# IMX7S_MEMORY.net
KiCad netlist of a schematic drawn in Altium Designer
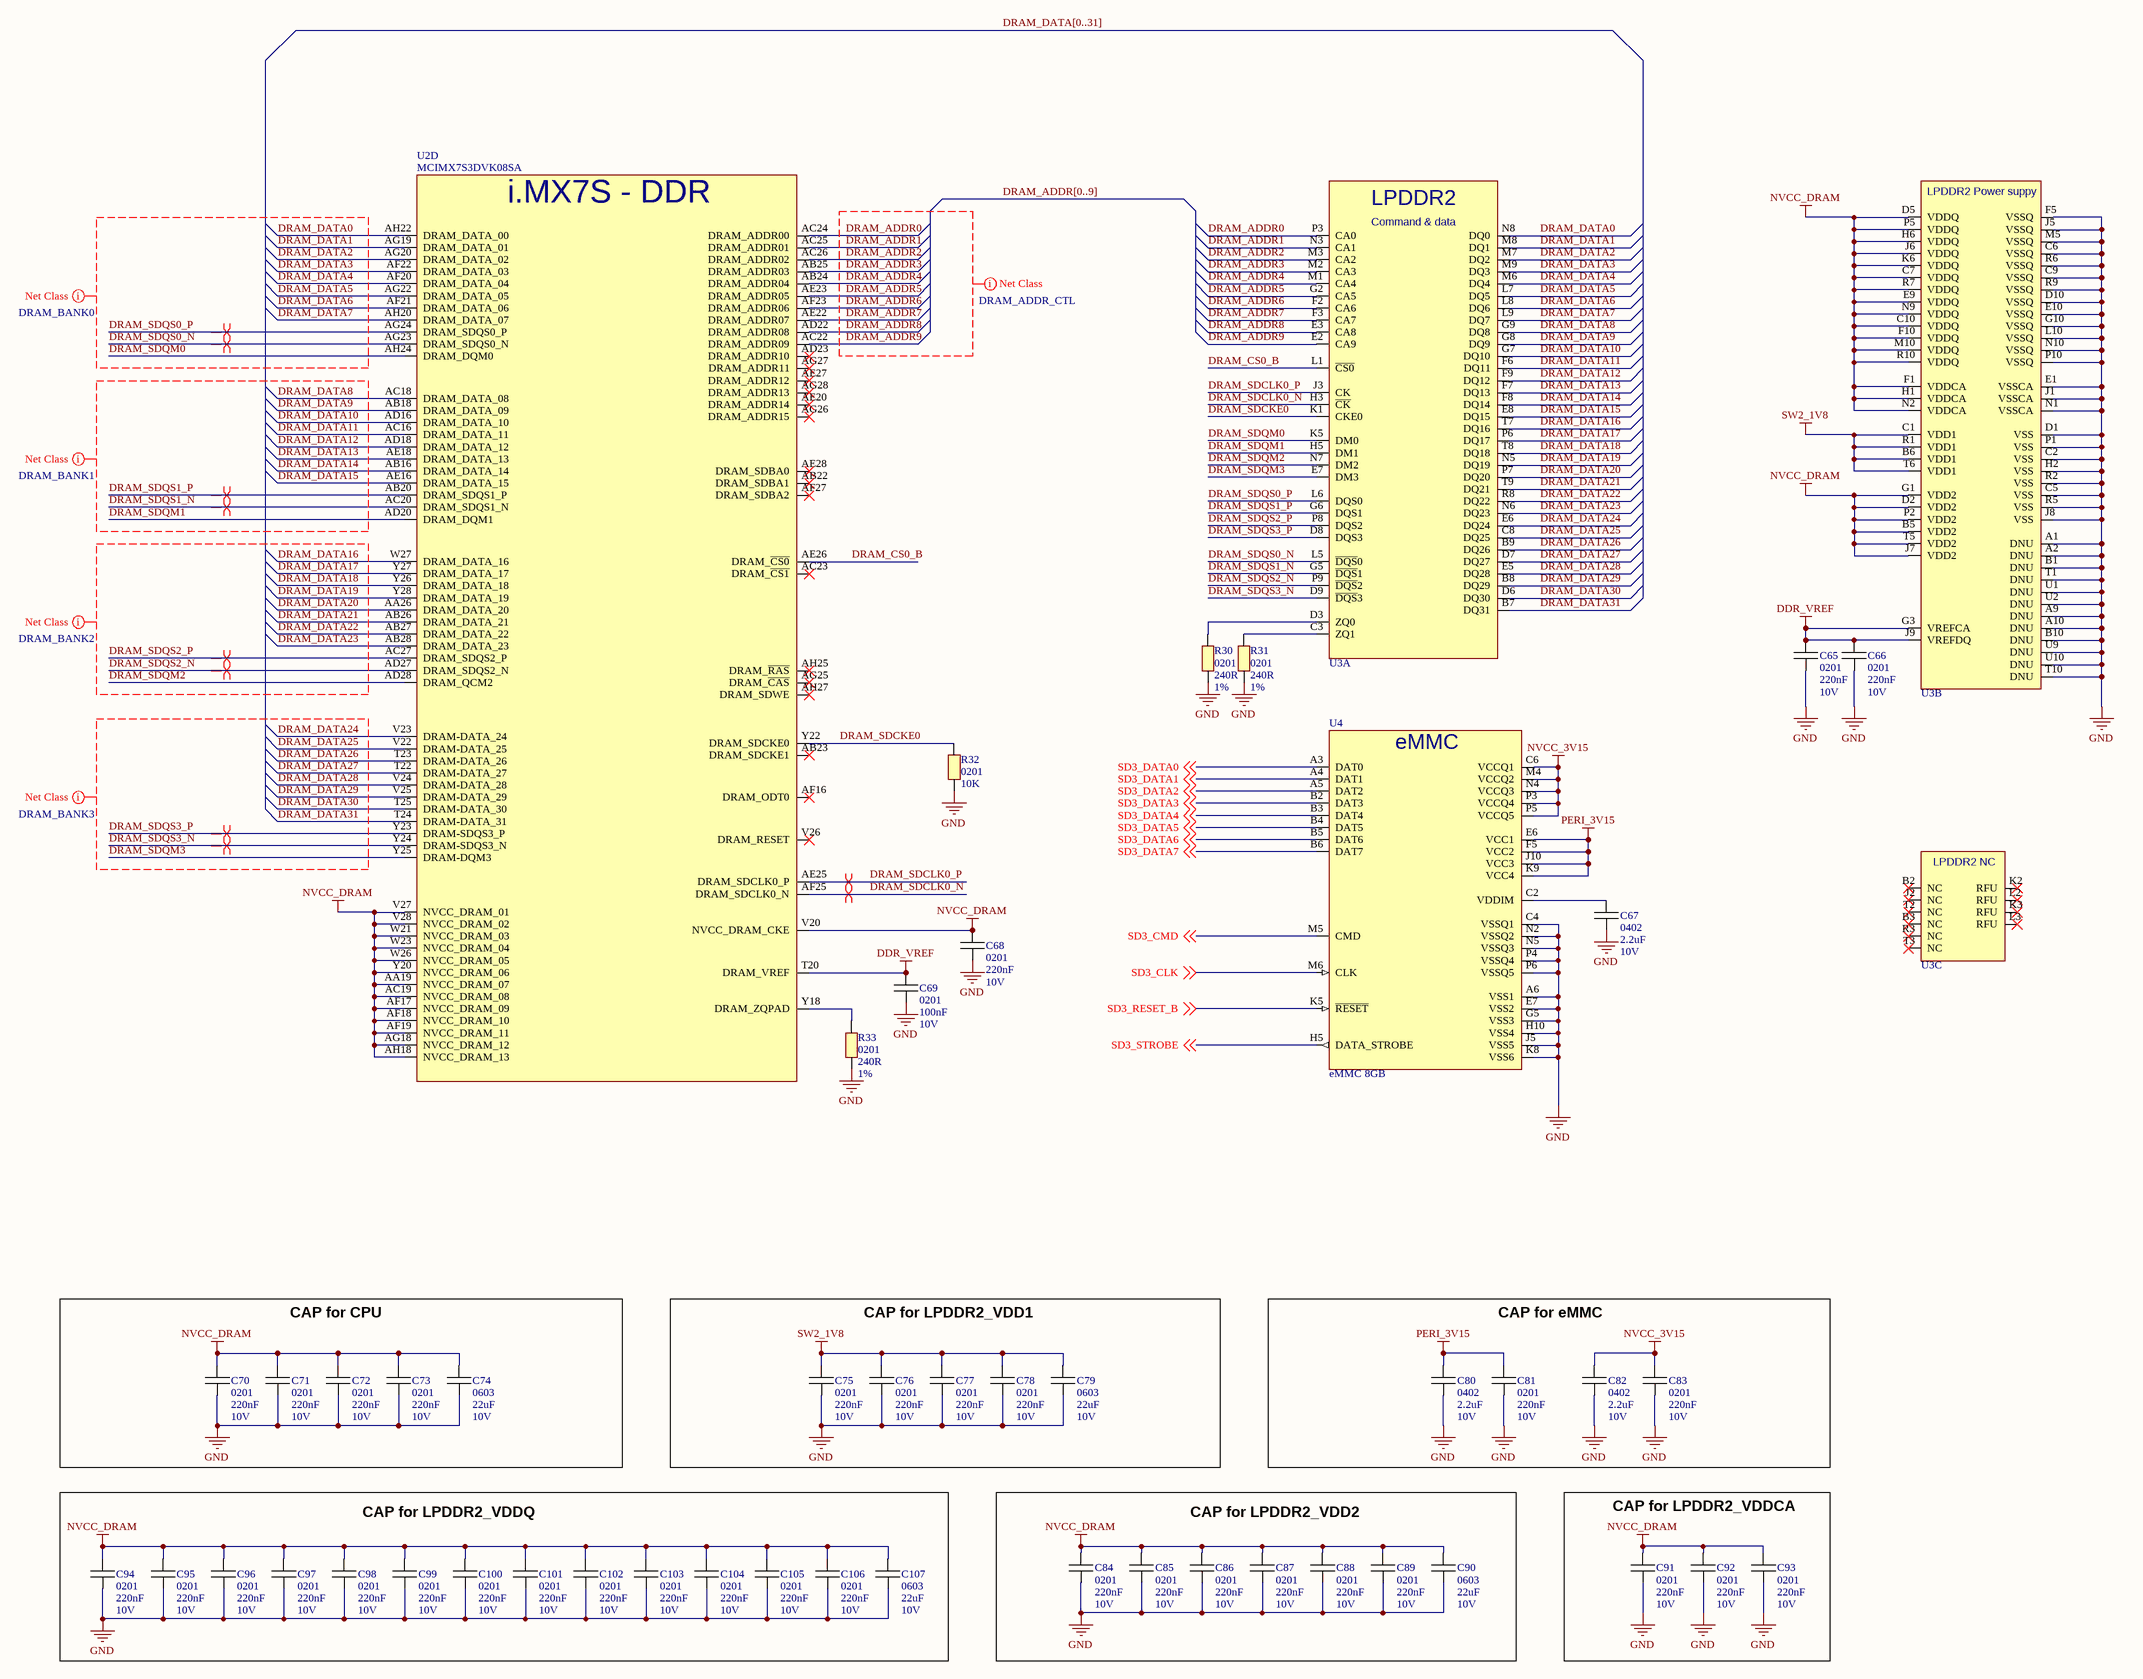
[diagram p0: IMX7S_MEMORY.SchDoc]

(export (version "E")
  (design (tool "Eeschema 10.0.6"))
  (components
    (comp (ref "C65")
      (value "220nF")
      (footprint "C0201")
      (fields
        (field (name "PACKAGE") "0201")
        (field (name "VOLTAGE") "10V")
        (field (name "TOLERANCE") "10%")
        (field (name "Comment") "C0201")
      )
      (libsource (lib "Schlib_IMX7") (part "C0201"))
    )
    (comp (ref "C66")
      (value "220nF")
      (footprint "C0201")
      (fields
        (field (name "PACKAGE") "0201")
        (field (name "VOLTAGE") "10V")
        (field (name "TOLERANCE") "10%")
        (field (name "Comment") "C0201")
      )
      (libsource (lib "Schlib_IMX7") (part "C0201"))
    )
    (comp (ref "C67")
      (value "2.2uF")
      (footprint "C0402")
      (fields
        (field (name "PACKAGE") "0402")
        (field (name "VOLTAGE") "10V")
        (field (name "TOLERANCE") "20%")
        (field (name "Comment") "C0402")
      )
      (libsource (lib "Schlib_IMX7") (part "C0402"))
    )
    (comp (ref "C68")
      (value "220nF")
      (footprint "C0201")
      (fields
        (field (name "PACKAGE") "0201")
        (field (name "VOLTAGE") "10V")
        (field (name "TOLERANCE") "10%")
        (field (name "Comment") "C0201")
      )
      (libsource (lib "Schlib_IMX7") (part "C0201"))
    )
    (comp (ref "C69")
      (value "100nF")
      (footprint "C0201")
      (fields
        (field (name "PACKAGE") "0201")
        (field (name "VOLTAGE") "10V")
        (field (name "TOLERANCE") "10%")
        (field (name "Comment") "C0201")
      )
      (libsource (lib "Schlib_IMX7") (part "C0201"))
    )
    (comp (ref "C70")
      (value "220nF")
      (footprint "C0201")
      (fields
        (field (name "PACKAGE") "0201")
        (field (name "VOLTAGE") "10V")
        (field (name "TOLERANCE") "10%")
        (field (name "Comment") "C0201")
      )
      (libsource (lib "Schlib_IMX7") (part "C0201"))
    )
    (comp (ref "C71")
      (value "220nF")
      (footprint "C0201")
      (fields
        (field (name "PACKAGE") "0201")
        (field (name "VOLTAGE") "10V")
        (field (name "TOLERANCE") "10%")
        (field (name "Comment") "C0201")
      )
      (libsource (lib "Schlib_IMX7") (part "C0201"))
    )
    (comp (ref "C72")
      (value "220nF")
      (footprint "C0201")
      (fields
        (field (name "PACKAGE") "0201")
        (field (name "VOLTAGE") "10V")
        (field (name "TOLERANCE") "10%")
        (field (name "Comment") "C0201")
      )
      (libsource (lib "Schlib_IMX7") (part "C0201"))
    )
    (comp (ref "C73")
      (value "220nF")
      (footprint "C0201")
      (fields
        (field (name "PACKAGE") "0201")
        (field (name "VOLTAGE") "10V")
        (field (name "TOLERANCE") "10%")
        (field (name "Comment") "C0201")
      )
      (libsource (lib "Schlib_IMX7") (part "C0201"))
    )
    (comp (ref "C74")
      (value "22uF")
      (footprint "C0603")
      (description "CAP, MLCC, X5R, 22UF, 10V, 0603")
      (fields
        (field (name "PACKAGE") "0603")
        (field (name "VOLTAGE") "10V")
        (field (name "TOLERANCE") "20%")
        (field (name "Comment") "C0603")
      )
      (libsource (lib "Schlib_IMX7") (part "C0603"))
    )
    (comp (ref "C75")
      (value "220nF")
      (footprint "C0201")
      (fields
        (field (name "PACKAGE") "0201")
        (field (name "VOLTAGE") "10V")
        (field (name "TOLERANCE") "10%")
        (field (name "Comment") "C0201")
      )
      (libsource (lib "Schlib_IMX7") (part "C0201"))
    )
    (comp (ref "C76")
      (value "220nF")
      (footprint "C0201")
      (fields
        (field (name "PACKAGE") "0201")
        (field (name "VOLTAGE") "10V")
        (field (name "TOLERANCE") "10%")
        (field (name "Comment") "C0201")
      )
      (libsource (lib "Schlib_IMX7") (part "C0201"))
    )
    (comp (ref "C77")
      (value "220nF")
      (footprint "C0201")
      (fields
        (field (name "PACKAGE") "0201")
        (field (name "VOLTAGE") "10V")
        (field (name "TOLERANCE") "10%")
        (field (name "Comment") "C0201")
      )
      (libsource (lib "Schlib_IMX7") (part "C0201"))
    )
    (comp (ref "C78")
      (value "220nF")
      (footprint "C0201")
      (fields
        (field (name "PACKAGE") "0201")
        (field (name "VOLTAGE") "10V")
        (field (name "TOLERANCE") "10%")
        (field (name "Comment") "C0201")
      )
      (libsource (lib "Schlib_IMX7") (part "C0201"))
    )
    (comp (ref "C79")
      (value "22uF")
      (footprint "C0603")
      (description "CAP, MLCC, X5R, 22UF, 10V, 0603")
      (fields
        (field (name "PACKAGE") "0603")
        (field (name "VOLTAGE") "10V")
        (field (name "TOLERANCE") "20%")
        (field (name "Comment") "C0603")
      )
      (libsource (lib "Schlib_IMX7") (part "C0603"))
    )
    (comp (ref "C80")
      (value "2.2uF")
      (footprint "C0402")
      (description "Cap Ceramic 2.2uF 10V X5R 10% SMD 0402 85C Paper T/R")
      (fields
        (field (name "PACKAGE") "0402")
        (field (name "VOLTAGE") "10V")
        (field (name "TOLERANCE") "10%")
        (field (name "Comment") "C0402")
      )
      (libsource (lib "Schlib_IMX7") (part "C0402"))
    )
    (comp (ref "C81")
      (value "220nF")
      (footprint "C0201")
      (fields
        (field (name "PACKAGE") "0201")
        (field (name "VOLTAGE") "10V")
        (field (name "TOLERANCE") "10%")
        (field (name "Comment") "C0201")
      )
      (libsource (lib "Schlib_IMX7") (part "C0201"))
    )
    (comp (ref "C82")
      (value "2.2uF")
      (footprint "C0402")
      (description "Cap Ceramic 2.2uF 10V X5R 10% SMD 0402 85C Paper T/R")
      (fields
        (field (name "PACKAGE") "0402")
        (field (name "VOLTAGE") "10V")
        (field (name "TOLERANCE") "10%")
        (field (name "Comment") "C0402")
      )
      (libsource (lib "Schlib_IMX7") (part "C0402"))
    )
    (comp (ref "C83")
      (value "220nF")
      (footprint "C0201")
      (fields
        (field (name "PACKAGE") "0201")
        (field (name "VOLTAGE") "10V")
        (field (name "TOLERANCE") "10%")
        (field (name "Comment") "C0201")
      )
      (libsource (lib "Schlib_IMX7") (part "C0201"))
    )
    (comp (ref "C84")
      (value "220nF")
      (footprint "C0201")
      (fields
        (field (name "PACKAGE") "0201")
        (field (name "VOLTAGE") "10V")
        (field (name "TOLERANCE") "10%")
        (field (name "Comment") "C0201")
      )
      (libsource (lib "Schlib_IMX7") (part "C0201"))
    )
    (comp (ref "C85")
      (value "220nF")
      (footprint "C0201")
      (fields
        (field (name "PACKAGE") "0201")
        (field (name "VOLTAGE") "10V")
        (field (name "TOLERANCE") "10%")
        (field (name "Comment") "C0201")
      )
      (libsource (lib "Schlib_IMX7") (part "C0201"))
    )
    (comp (ref "C86")
      (value "220nF")
      (footprint "C0201")
      (fields
        (field (name "PACKAGE") "0201")
        (field (name "VOLTAGE") "10V")
        (field (name "TOLERANCE") "10%")
        (field (name "Comment") "C0201")
      )
      (libsource (lib "Schlib_IMX7") (part "C0201"))
    )
    (comp (ref "C87")
      (value "220nF")
      (footprint "C0201")
      (fields
        (field (name "PACKAGE") "0201")
        (field (name "VOLTAGE") "10V")
        (field (name "TOLERANCE") "10%")
        (field (name "Comment") "C0201")
      )
      (libsource (lib "Schlib_IMX7") (part "C0201"))
    )
    (comp (ref "C88")
      (value "220nF")
      (footprint "C0201")
      (fields
        (field (name "PACKAGE") "0201")
        (field (name "VOLTAGE") "10V")
        (field (name "TOLERANCE") "10%")
        (field (name "Comment") "C0201")
      )
      (libsource (lib "Schlib_IMX7") (part "C0201"))
    )
    (comp (ref "C89")
      (value "220nF")
      (footprint "C0201")
      (fields
        (field (name "PACKAGE") "0201")
        (field (name "VOLTAGE") "10V")
        (field (name "TOLERANCE") "10%")
        (field (name "Comment") "C0201")
      )
      (libsource (lib "Schlib_IMX7") (part "C0201"))
    )
    (comp (ref "C90")
      (value "22uF")
      (footprint "C0603")
      (description "CAP, MLCC, X5R, 22UF, 10V, 0603")
      (fields
        (field (name "PACKAGE") "0603")
        (field (name "VOLTAGE") "10V")
        (field (name "TOLERANCE") "20%")
        (field (name "Comment") "C0603")
      )
      (libsource (lib "Schlib_IMX7") (part "C0603"))
    )
    (comp (ref "C91")
      (value "220nF")
      (footprint "C0201")
      (fields
        (field (name "PACKAGE") "0201")
        (field (name "VOLTAGE") "10V")
        (field (name "TOLERANCE") "10%")
        (field (name "Comment") "C0201")
      )
      (libsource (lib "Schlib_IMX7") (part "C0201"))
    )
    (comp (ref "C92")
      (value "220nF")
      (footprint "C0201")
      (fields
        (field (name "PACKAGE") "0201")
        (field (name "VOLTAGE") "10V")
        (field (name "TOLERANCE") "10%")
        (field (name "Comment") "C0201")
      )
      (libsource (lib "Schlib_IMX7") (part "C0201"))
    )
    (comp (ref "C93")
      (value "220nF")
      (footprint "C0201")
      (fields
        (field (name "PACKAGE") "0201")
        (field (name "VOLTAGE") "10V")
        (field (name "TOLERANCE") "10%")
        (field (name "Comment") "C0201")
      )
      (libsource (lib "Schlib_IMX7") (part "C0201"))
    )
    (comp (ref "C94")
      (value "220nF")
      (footprint "C0201")
      (fields
        (field (name "PACKAGE") "0201")
        (field (name "VOLTAGE") "10V")
        (field (name "TOLERANCE") "10%")
        (field (name "Comment") "C0201")
      )
      (libsource (lib "Schlib_IMX7") (part "C0201"))
    )
    (comp (ref "C95")
      (value "220nF")
      (footprint "C0201")
      (fields
        (field (name "PACKAGE") "0201")
        (field (name "VOLTAGE") "10V")
        (field (name "TOLERANCE") "10%")
        (field (name "Comment") "C0201")
      )
      (libsource (lib "Schlib_IMX7") (part "C0201"))
    )
    (comp (ref "C96")
      (value "220nF")
      (footprint "C0201")
      (fields
        (field (name "PACKAGE") "0201")
        (field (name "VOLTAGE") "10V")
        (field (name "TOLERANCE") "10%")
        (field (name "Comment") "C0201")
      )
      (libsource (lib "Schlib_IMX7") (part "C0201"))
    )
    (comp (ref "C97")
      (value "220nF")
      (footprint "C0201")
      (fields
        (field (name "PACKAGE") "0201")
        (field (name "VOLTAGE") "10V")
        (field (name "TOLERANCE") "10%")
        (field (name "Comment") "C0201")
      )
      (libsource (lib "Schlib_IMX7") (part "C0201"))
    )
    (comp (ref "C98")
      (value "220nF")
      (footprint "C0201")
      (fields
        (field (name "PACKAGE") "0201")
        (field (name "VOLTAGE") "10V")
        (field (name "TOLERANCE") "10%")
        (field (name "Comment") "C0201")
      )
      (libsource (lib "Schlib_IMX7") (part "C0201"))
    )
    (comp (ref "C99")
      (value "220nF")
      (footprint "C0201")
      (fields
        (field (name "PACKAGE") "0201")
        (field (name "VOLTAGE") "10V")
        (field (name "TOLERANCE") "10%")
        (field (name "Comment") "C0201")
      )
      (libsource (lib "Schlib_IMX7") (part "C0201"))
    )
    (comp (ref "C100")
      (value "220nF")
      (footprint "C0201")
      (fields
        (field (name "PACKAGE") "0201")
        (field (name "VOLTAGE") "10V")
        (field (name "TOLERANCE") "10%")
        (field (name "Comment") "C0201")
      )
      (libsource (lib "Schlib_IMX7") (part "C0201"))
    )
    (comp (ref "C101")
      (value "220nF")
      (footprint "C0201")
      (fields
        (field (name "PACKAGE") "0201")
        (field (name "VOLTAGE") "10V")
        (field (name "TOLERANCE") "10%")
        (field (name "Comment") "C0201")
      )
      (libsource (lib "Schlib_IMX7") (part "C0201"))
    )
    (comp (ref "C102")
      (value "220nF")
      (footprint "C0201")
      (fields
        (field (name "PACKAGE") "0201")
        (field (name "VOLTAGE") "10V")
        (field (name "TOLERANCE") "10%")
        (field (name "Comment") "C0201")
      )
      (libsource (lib "Schlib_IMX7") (part "C0201"))
    )
    (comp (ref "C103")
      (value "220nF")
      (footprint "C0201")
      (fields
        (field (name "PACKAGE") "0201")
        (field (name "VOLTAGE") "10V")
        (field (name "TOLERANCE") "10%")
        (field (name "Comment") "C0201")
      )
      (libsource (lib "Schlib_IMX7") (part "C0201"))
    )
    (comp (ref "C104")
      (value "220nF")
      (footprint "C0201")
      (fields
        (field (name "PACKAGE") "0201")
        (field (name "VOLTAGE") "10V")
        (field (name "TOLERANCE") "10%")
        (field (name "Comment") "C0201")
      )
      (libsource (lib "Schlib_IMX7") (part "C0201"))
    )
    (comp (ref "C105")
      (value "220nF")
      (footprint "C0201")
      (fields
        (field (name "PACKAGE") "0201")
        (field (name "VOLTAGE") "10V")
        (field (name "TOLERANCE") "10%")
        (field (name "Comment") "C0201")
      )
      (libsource (lib "Schlib_IMX7") (part "C0201"))
    )
    (comp (ref "C106")
      (value "220nF")
      (footprint "C0201")
      (fields
        (field (name "PACKAGE") "0201")
        (field (name "VOLTAGE") "10V")
        (field (name "TOLERANCE") "10%")
        (field (name "Comment") "C0201")
      )
      (libsource (lib "Schlib_IMX7") (part "C0201"))
    )
    (comp (ref "C107")
      (value "22uF")
      (footprint "C0603")
      (description "CAP, MLCC, X5R, 22UF, 10V, 0603")
      (fields
        (field (name "PACKAGE") "0603")
        (field (name "VOLTAGE") "10V")
        (field (name "TOLERANCE") "20%")
        (field (name "Comment") "C0603")
      )
      (libsource (lib "Schlib_IMX7") (part "C0603"))
    )
    (comp (ref "R30")
      (value "240R")
      (footprint "R0201")
      (fields
        (field (name "PACKAGE") "0201")
        (field (name "VOLTAGE") "1%")
        (field (name "TOLERANCE") "1%")
        (field (name "Comment") "R0201")
      )
      (libsource (lib "Schlib_IMX7") (part "R0201"))
    )
    (comp (ref "R31")
      (value "240R")
      (footprint "R0201")
      (fields
        (field (name "PACKAGE") "0201")
        (field (name "VOLTAGE") "1%")
        (field (name "TOLERANCE") "1%")
        (field (name "Comment") "R0201")
      )
      (libsource (lib "Schlib_IMX7") (part "R0201"))
    )
    (comp (ref "R32")
      (value "10K")
      (footprint "R0201")
      (description "RESISTOR, 0201, 0.05W, 1%, 10K")
      (fields (field (name "PACKAGE") "0201") (field (name "VOLTAGE") "0V") (field (name "TOLERANCE") "1%"))
      (libsource (lib "Schlib_IMX7") (part "R0201"))
    )
    (comp (ref "R33")
      (value "240R")
      (footprint "R0201")
      (fields
        (field (name "PACKAGE") "0201")
        (field (name "VOLTAGE") "1%")
        (field (name "TOLERANCE") "1%")
        (field (name "Comment") "R0201")
      )
      (libsource (lib "Schlib_IMX7") (part "R0201"))
    )
    (comp (ref "U2")
      (value "MCIMX7S3DVK08SA")
      (footprint "BGA 488 PIN")
      (libsource (lib "Schlib_IMX7") (part "MCIMX7S3DVK08SD"))
    )
    (comp (ref "U3")
      (value "EDB2432B4MA-1DAAT-F-R")
      (footprint "DDR_VFBGA")
      (libsource (lib "Schlib_IMX7") (part "EDB2432B4MA-1DAAT-F-R"))
    )
    (comp (ref "U4")
      (value "eMMC 8GB")
      (footprint "VFBGA")
      (libsource (lib "Schlib_IMX7") (part "MTFC8GAKAJCN-4M IT"))
    )
  )
  (nets
    (net (code "1") (name "/DRAM_ADDR0") (class "Default")
      (node (ref "U2") (pin "AC24") (pinfunction "DRAM_ADDR00_AC24") (pintype "passive"))
      (node (ref "U3") (pin "P3") (pinfunction "CA0_P3") (pintype "passive"))
    )
    (net (code "2") (name "/DRAM_ADDR1") (class "Default")
      (node (ref "U2") (pin "AC25") (pinfunction "DRAM_ADDR01_AC25") (pintype "passive"))
      (node (ref "U3") (pin "N3") (pinfunction "CA1_N3") (pintype "passive"))
    )
    (net (code "3") (name "/DRAM_ADDR2") (class "Default")
      (node (ref "U2") (pin "AC26") (pinfunction "DRAM_ADDR02_AC26") (pintype "passive"))
      (node (ref "U3") (pin "M3") (pinfunction "CA2_M3") (pintype "passive"))
    )
    (net (code "4") (name "/DRAM_ADDR3") (class "Default")
      (node (ref "U2") (pin "AB25") (pinfunction "DRAM_ADDR03_AB25") (pintype "passive"))
      (node (ref "U3") (pin "M2") (pinfunction "CA3_M2") (pintype "passive"))
    )
    (net (code "5") (name "/DRAM_ADDR4") (class "Default")
      (node (ref "U2") (pin "AB24") (pinfunction "DRAM_ADDR04_AB24") (pintype "passive"))
      (node (ref "U3") (pin "M1") (pinfunction "CA4_M1") (pintype "passive"))
    )
    (net (code "6") (name "/DRAM_ADDR5") (class "Default")
      (node (ref "U2") (pin "AE23") (pinfunction "DRAM_ADDR05_AE23") (pintype "passive"))
      (node (ref "U3") (pin "G2") (pinfunction "CA5_G2") (pintype "passive"))
    )
    (net (code "7") (name "/DRAM_ADDR6") (class "Default")
      (node (ref "U2") (pin "AF23") (pinfunction "DRAM_ADDR06_AF23") (pintype "passive"))
      (node (ref "U3") (pin "F2") (pinfunction "CA6_F2") (pintype "passive"))
    )
    (net (code "8") (name "/DRAM_ADDR7") (class "Default")
      (node (ref "U2") (pin "AE22") (pinfunction "DRAM_ADDR07_AE22") (pintype "passive"))
      (node (ref "U3") (pin "F3") (pinfunction "CA7_F3") (pintype "passive"))
    )
    (net (code "9") (name "/DRAM_ADDR8") (class "Default")
      (node (ref "U2") (pin "AD22") (pinfunction "DRAM_ADDR08_AD22") (pintype "passive"))
      (node (ref "U3") (pin "E3") (pinfunction "CA8_E3") (pintype "passive"))
    )
    (net (code "10") (name "/DRAM_ADDR9") (class "Default")
      (node (ref "U2") (pin "AC22") (pinfunction "DRAM_ADDR09_AC22") (pintype "passive"))
      (node (ref "U3") (pin "E2") (pinfunction "CA9_E2") (pintype "passive"))
    )
    (net (code "12") (name "/DRAM_CS0_B") (class "Default")
      (node (ref "U2") (pin "AE26") (pinfunction "DRAM_~{CS0}_AE26") (pintype "passive"))
      (node (ref "U3") (pin "L1") (pinfunction "~{CS0}_L1") (pintype "passive"))
    )
    (net (code "13") (name "/DRAM_DATA0") (class "Default")
      (node (ref "U2") (pin "AH22") (pinfunction "DRAM_DATA_00_AH22") (pintype "passive"))
      (node (ref "U3") (pin "N8") (pinfunction "DQ0_N8") (pintype "passive"))
    )
    (net (code "14") (name "/DRAM_DATA1") (class "Default")
      (node (ref "U2") (pin "AG19") (pinfunction "DRAM_DATA_01_AG19") (pintype "passive"))
      (node (ref "U3") (pin "M8") (pinfunction "DQ1_M8") (pintype "passive"))
    )
    (net (code "15") (name "/DRAM_DATA2") (class "Default")
      (node (ref "U2") (pin "AG20") (pinfunction "DRAM_DATA_02_AG20") (pintype "passive"))
      (node (ref "U3") (pin "M7") (pinfunction "DQ2_M7") (pintype "passive"))
    )
    (net (code "16") (name "/DRAM_DATA3") (class "Default")
      (node (ref "U2") (pin "AF22") (pinfunction "DRAM_DATA_03_AF22") (pintype "passive"))
      (node (ref "U3") (pin "M9") (pinfunction "DQ3_M9") (pintype "passive"))
    )
    (net (code "17") (name "/DRAM_DATA4") (class "Default")
      (node (ref "U2") (pin "AF20") (pinfunction "DRAM_DATA_04_AF20") (pintype "passive"))
      (node (ref "U3") (pin "M6") (pinfunction "DQ4_M6") (pintype "passive"))
    )
    (net (code "18") (name "/DRAM_DATA5") (class "Default")
      (node (ref "U2") (pin "AG22") (pinfunction "DRAM_DATA_05_AG22") (pintype "passive"))
      (node (ref "U3") (pin "L7") (pinfunction "DQ5_L7") (pintype "passive"))
    )
    (net (code "19") (name "/DRAM_DATA6") (class "Default")
      (node (ref "U2") (pin "AF21") (pinfunction "DRAM_DATA_06_AF21") (pintype "passive"))
      (node (ref "U3") (pin "L8") (pinfunction "DQ6_L8") (pintype "passive"))
    )
    (net (code "20") (name "/DRAM_DATA7") (class "Default")
      (node (ref "U2") (pin "AH20") (pinfunction "DRAM_DATA_07_AH20") (pintype "passive"))
      (node (ref "U3") (pin "L9") (pinfunction "DQ7_L9") (pintype "passive"))
    )
    (net (code "21") (name "/DRAM_DATA8") (class "Default")
      (node (ref "U2") (pin "AC18") (pinfunction "DRAM_DATA_08_AC18") (pintype "passive"))
      (node (ref "U3") (pin "G9") (pinfunction "DQ8_G9") (pintype "passive"))
    )
    (net (code "22") (name "/DRAM_DATA9") (class "Default")
      (node (ref "U2") (pin "AB18") (pinfunction "DRAM_DATA_09_AB18") (pintype "passive"))
      (node (ref "U3") (pin "G8") (pinfunction "DQ9_G8") (pintype "passive"))
    )
    (net (code "23") (name "/DRAM_DATA10") (class "Default")
      (node (ref "U2") (pin "AD16") (pinfunction "DRAM_DATA_10_AD16") (pintype "passive"))
      (node (ref "U3") (pin "G7") (pinfunction "DQ10_G7") (pintype "passive"))
    )
    (net (code "24") (name "/DRAM_DATA11") (class "Default")
      (node (ref "U2") (pin "AC16") (pinfunction "DRAM_DATA_11_AC16") (pintype "passive"))
      (node (ref "U3") (pin "F6") (pinfunction "DQ11_F6") (pintype "passive"))
    )
    (net (code "25") (name "/DRAM_DATA12") (class "Default")
      (node (ref "U2") (pin "AD18") (pinfunction "DRAM_DATA_12_AD18") (pintype "passive"))
      (node (ref "U3") (pin "F9") (pinfunction "DQ12_F9") (pintype "passive"))
    )
    (net (code "26") (name "/DRAM_DATA13") (class "Default")
      (node (ref "U2") (pin "AE18") (pinfunction "DRAM_DATA_13_AE18") (pintype "passive"))
      (node (ref "U3") (pin "F7") (pinfunction "DQ13_F7") (pintype "passive"))
    )
    (net (code "27") (name "/DRAM_DATA14") (class "Default")
      (node (ref "U2") (pin "AB16") (pinfunction "DRAM_DATA_14_AB16") (pintype "passive"))
      (node (ref "U3") (pin "F8") (pinfunction "DQ14_F8") (pintype "passive"))
    )
    (net (code "28") (name "/DRAM_DATA15") (class "Default")
      (node (ref "U2") (pin "AE16") (pinfunction "DRAM_DATA_15_AE16") (pintype "passive"))
      (node (ref "U3") (pin "E8") (pinfunction "DQ15_E8") (pintype "passive"))
    )
    (net (code "29") (name "/DRAM_DATA16") (class "Default")
      (node (ref "U2") (pin "W27") (pinfunction "DRAM_DATA_16_W27") (pintype "passive"))
      (node (ref "U3") (pin "T7") (pinfunction "DQ16_T7") (pintype "passive"))
    )
    (net (code "30") (name "/DRAM_DATA17") (class "Default")
      (node (ref "U2") (pin "Y27") (pinfunction "DRAM_DATA_17_Y27") (pintype "passive"))
      (node (ref "U3") (pin "P6") (pinfunction "DQ17_P6") (pintype "passive"))
    )
    (net (code "31") (name "/DRAM_DATA18") (class "Default")
      (node (ref "U2") (pin "Y26") (pinfunction "DRAM_DATA_18_Y26") (pintype "passive"))
      (node (ref "U3") (pin "T8") (pinfunction "DQ18_T8") (pintype "passive"))
    )
    (net (code "32") (name "/DRAM_DATA19") (class "Default")
      (node (ref "U2") (pin "Y28") (pinfunction "DRAM_DATA_19_Y28") (pintype "passive"))
      (node (ref "U3") (pin "N5") (pinfunction "DQ19_N5") (pintype "passive"))
    )
    (net (code "33") (name "/DRAM_DATA20") (class "Default")
      (node (ref "U2") (pin "AA26") (pinfunction "DRAM_DATA_20_AA26") (pintype "passive"))
      (node (ref "U3") (pin "P7") (pinfunction "DQ20_P7") (pintype "passive"))
    )
    (net (code "34") (name "/DRAM_DATA21") (class "Default")
      (node (ref "U2") (pin "AB26") (pinfunction "DRAM_DATA_21_AB26") (pintype "passive"))
      (node (ref "U3") (pin "T9") (pinfunction "DQ21_T9") (pintype "passive"))
    )
    (net (code "35") (name "/DRAM_DATA22") (class "Default")
      (node (ref "U2") (pin "AB27") (pinfunction "DRAM_DATA_22_AB27") (pintype "passive"))
      (node (ref "U3") (pin "R8") (pinfunction "DQ22_R8") (pintype "passive"))
    )
    (net (code "36") (name "/DRAM_DATA23") (class "Default")
      (node (ref "U2") (pin "AB28") (pinfunction "DRAM_DATA_23_AB28") (pintype "passive"))
      (node (ref "U3") (pin "N6") (pinfunction "DQ23_N6") (pintype "passive"))
    )
    (net (code "37") (name "/DRAM_DATA24") (class "Default")
      (node (ref "U2") (pin "V23") (pinfunction "DRAM-DATA_24_V23") (pintype "passive"))
      (node (ref "U3") (pin "E6") (pinfunction "DQ24_E6") (pintype "passive"))
    )
    (net (code "38") (name "/DRAM_DATA25") (class "Default")
      (node (ref "U2") (pin "V22") (pinfunction "DRAM-DATA_25_V22") (pintype "passive"))
      (node (ref "U3") (pin "C8") (pinfunction "DQ25_C8") (pintype "passive"))
    )
    (net (code "39") (name "/DRAM_DATA26") (class "Default")
      (node (ref "U2") (pin "T23") (pinfunction "DRAM-DATA_26_T23") (pintype "passive"))
      (node (ref "U3") (pin "B9") (pinfunction "DQ26_B9") (pintype "passive"))
    )
    (net (code "40") (name "/DRAM_DATA27") (class "Default")
      (node (ref "U2") (pin "T22") (pinfunction "DRAM-DATA_27_T22") (pintype "passive"))
      (node (ref "U3") (pin "D7") (pinfunction "DQ27_D7") (pintype "passive"))
    )
    (net (code "41") (name "/DRAM_DATA28") (class "Default")
      (node (ref "U2") (pin "V24") (pinfunction "DRAM-DATA_28_V24") (pintype "passive"))
      (node (ref "U3") (pin "E5") (pinfunction "DQ28_E5") (pintype "passive"))
    )
    (net (code "42") (name "/DRAM_DATA29") (class "Default")
      (node (ref "U2") (pin "V25") (pinfunction "DRAM-DATA_29_V25") (pintype "passive"))
      (node (ref "U3") (pin "B8") (pinfunction "DQ29_B8") (pintype "passive"))
    )
    (net (code "43") (name "/DRAM_DATA30") (class "Default")
      (node (ref "U2") (pin "T25") (pinfunction "DRAM-DATA_30_T25") (pintype "passive"))
      (node (ref "U3") (pin "D6") (pinfunction "DQ30_D6") (pintype "passive"))
    )
    (net (code "44") (name "/DRAM_DATA31") (class "Default")
      (node (ref "U2") (pin "T24") (pinfunction "DRAM-DATA_31_T24") (pintype "passive"))
      (node (ref "U3") (pin "B7") (pinfunction "DQ31_B7") (pintype "passive"))
    )
    (net (code "46") (name "/DRAM_SDCKE0") (class "Default")
      (node (ref "R32") (pin "2") (pinfunction "2_2") (pintype "passive"))
      (node (ref "U2") (pin "Y22") (pinfunction "DRAM_SDCKE0_Y22") (pintype "passive"))
      (node (ref "U3") (pin "K1") (pinfunction "CKE0_K1") (pintype "passive"))
    )
    (net (code "47") (name "/DRAM_SDCLK0_N") (class "Default")
      (node (ref "U2") (pin "AF25") (pinfunction "DRAM_SDCLK0_N_AF25") (pintype "passive"))
      (node (ref "U3") (pin "H3") (pinfunction "~{CK}_H3") (pintype "passive"))
    )
    (net (code "48") (name "/DRAM_SDCLK0_P") (class "Default")
      (node (ref "U2") (pin "AE25") (pinfunction "DRAM_SDCLK0_P_AE25") (pintype "passive"))
      (node (ref "U3") (pin "J3") (pinfunction "CK_J3") (pintype "passive"))
    )
    (net (code "49") (name "/DRAM_SDQM0") (class "Default")
      (node (ref "U2") (pin "AH24") (pinfunction "DRAM_DQM0_AH24") (pintype "passive"))
      (node (ref "U3") (pin "K5") (pinfunction "DM0_K5") (pintype "passive"))
    )
    (net (code "50") (name "/DRAM_SDQM1") (class "Default")
      (node (ref "U2") (pin "AD20") (pinfunction "DRAM_DQM1_AD20") (pintype "passive"))
      (node (ref "U3") (pin "H5") (pinfunction "DM1_H5") (pintype "passive"))
    )
    (net (code "51") (name "/DRAM_SDQM2") (class "Default")
      (node (ref "U2") (pin "AD28") (pinfunction "DRAM_QCM2_AD28") (pintype "passive"))
      (node (ref "U3") (pin "N7") (pinfunction "DM2_N7") (pintype "passive"))
    )
    (net (code "52") (name "/DRAM_SDQM3") (class "Default")
      (node (ref "U2") (pin "Y25") (pinfunction "DRAM-DQM3_Y25") (pintype "passive"))
      (node (ref "U3") (pin "E7") (pinfunction "DM3_E7") (pintype "passive"))
    )
    (net (code "53") (name "/DRAM_SDQS0_N") (class "Default")
      (node (ref "U2") (pin "AG23") (pinfunction "DRAM_SDQS0_N_AG23") (pintype "passive"))
      (node (ref "U3") (pin "L5") (pinfunction "~{DQS}0_L5") (pintype "passive"))
    )
    (net (code "54") (name "/DRAM_SDQS0_P") (class "Default")
      (node (ref "U2") (pin "AG24") (pinfunction "DRAM_SDQS0_P_AG24") (pintype "passive"))
      (node (ref "U3") (pin "L6") (pinfunction "DQS0_L6") (pintype "passive"))
    )
    (net (code "55") (name "/DRAM_SDQS1_N") (class "Default")
      (node (ref "U2") (pin "AC20") (pinfunction "DRAM_SDQS1_N_AC20") (pintype "passive"))
      (node (ref "U3") (pin "G5") (pinfunction "~{DQS}1_G5") (pintype "passive"))
    )
    (net (code "56") (name "/DRAM_SDQS1_P") (class "Default")
      (node (ref "U2") (pin "AB20") (pinfunction "DRAM_SDQS1_P_AB20") (pintype "passive"))
      (node (ref "U3") (pin "G6") (pinfunction "DQS1_G6") (pintype "passive"))
    )
    (net (code "57") (name "/DRAM_SDQS2_N") (class "Default")
      (node (ref "U2") (pin "AD27") (pinfunction "DRAM_SDQS2_N_AD27") (pintype "passive"))
      (node (ref "U3") (pin "P9") (pinfunction "~{DQS}2_P9") (pintype "passive"))
    )
    (net (code "58") (name "/DRAM_SDQS2_P") (class "Default")
      (node (ref "U2") (pin "AC27") (pinfunction "DRAM_SDQS2_P_AC27") (pintype "passive"))
      (node (ref "U3") (pin "P8") (pinfunction "DQS2_P8") (pintype "passive"))
    )
    (net (code "59") (name "/DRAM_SDQS3_N") (class "Default")
      (node (ref "U2") (pin "Y24") (pinfunction "DRAM-SDQS3_N_Y24") (pintype "passive"))
      (node (ref "U3") (pin "D9") (pinfunction "~{DQS}3_D9") (pintype "passive"))
    )
    (net (code "60") (name "/DRAM_SDQS3_P") (class "Default")
      (node (ref "U2") (pin "Y23") (pinfunction "DRAM-SDQS3_P_Y23") (pintype "passive"))
      (node (ref "U3") (pin "D8") (pinfunction "DQS3_D8") (pintype "passive"))
    )
    (net (code "61") (name "DDR_VREF") (class "Default")
      (node (ref "C65") (pin "2") (pinfunction "2_2") (pintype "passive"))
      (node (ref "C66") (pin "2") (pinfunction "2_2") (pintype "passive"))
      (node (ref "C69") (pin "2") (pinfunction "2_2") (pintype "passive"))
      (node (ref "U2") (pin "T20") (pinfunction "DRAM_VREF_T20") (pintype "passive"))
      (node (ref "U3") (pin "G3") (pinfunction "VREFCA_G3") (pintype "passive"))
      (node (ref "U3") (pin "J9") (pinfunction "VREFDQ_J9") (pintype "passive"))
    )
    (net (code "62") (name "GND") (class "Default")
      (node (ref "C100") (pin "1") (pinfunction "1_1") (pintype "passive"))
      (node (ref "C101") (pin "1") (pinfunction "1_1") (pintype "passive"))
      (node (ref "C102") (pin "1") (pinfunction "1_1") (pintype "passive"))
      (node (ref "C103") (pin "1") (pinfunction "1_1") (pintype "passive"))
      (node (ref "C104") (pin "1") (pinfunction "1_1") (pintype "passive"))
      (node (ref "C105") (pin "1") (pinfunction "1_1") (pintype "passive"))
      (node (ref "C106") (pin "1") (pinfunction "1_1") (pintype "passive"))
      (node (ref "C107") (pin "1") (pinfunction "1_1") (pintype "passive"))
      (node (ref "C65") (pin "1") (pinfunction "1_1") (pintype "passive"))
      (node (ref "C66") (pin "1") (pinfunction "1_1") (pintype "passive"))
      (node (ref "C67") (pin "1") (pinfunction "1_1") (pintype "passive"))
      (node (ref "C68") (pin "1") (pinfunction "1_1") (pintype "passive"))
      (node (ref "C69") (pin "1") (pinfunction "1_1") (pintype "passive"))
      (node (ref "C70") (pin "1") (pinfunction "1_1") (pintype "passive"))
      (node (ref "C71") (pin "1") (pinfunction "1_1") (pintype "passive"))
      (node (ref "C72") (pin "1") (pinfunction "1_1") (pintype "passive"))
      (node (ref "C73") (pin "1") (pinfunction "1_1") (pintype "passive"))
      (node (ref "C74") (pin "1") (pinfunction "1_1") (pintype "passive"))
      (node (ref "C75") (pin "1") (pinfunction "1_1") (pintype "passive"))
      (node (ref "C76") (pin "1") (pinfunction "1_1") (pintype "passive"))
      (node (ref "C77") (pin "1") (pinfunction "1_1") (pintype "passive"))
      (node (ref "C78") (pin "1") (pinfunction "1_1") (pintype "passive"))
      (node (ref "C79") (pin "1") (pinfunction "1_1") (pintype "passive"))
      (node (ref "C80") (pin "1") (pinfunction "1_1") (pintype "passive"))
      (node (ref "C81") (pin "1") (pinfunction "1_1") (pintype "passive"))
      (node (ref "C82") (pin "1") (pinfunction "1_1") (pintype "passive"))
      (node (ref "C83") (pin "1") (pinfunction "1_1") (pintype "passive"))
      (node (ref "C84") (pin "1") (pinfunction "1_1") (pintype "passive"))
      (node (ref "C85") (pin "1") (pinfunction "1_1") (pintype "passive"))
      (node (ref "C86") (pin "1") (pinfunction "1_1") (pintype "passive"))
      (node (ref "C87") (pin "1") (pinfunction "1_1") (pintype "passive"))
      (node (ref "C88") (pin "1") (pinfunction "1_1") (pintype "passive"))
      (node (ref "C89") (pin "1") (pinfunction "1_1") (pintype "passive"))
      (node (ref "C90") (pin "1") (pinfunction "1_1") (pintype "passive"))
      (node (ref "C91") (pin "1") (pinfunction "1_1") (pintype "passive"))
      (node (ref "C92") (pin "1") (pinfunction "1_1") (pintype "passive"))
      (node (ref "C93") (pin "1") (pinfunction "1_1") (pintype "passive"))
      (node (ref "C94") (pin "1") (pinfunction "1_1") (pintype "passive"))
      (node (ref "C95") (pin "1") (pinfunction "1_1") (pintype "passive"))
      (node (ref "C96") (pin "1") (pinfunction "1_1") (pintype "passive"))
      (node (ref "C97") (pin "1") (pinfunction "1_1") (pintype "passive"))
      (node (ref "C98") (pin "1") (pinfunction "1_1") (pintype "passive"))
      (node (ref "C99") (pin "1") (pinfunction "1_1") (pintype "passive"))
      (node (ref "R30") (pin "1") (pinfunction "1_1") (pintype "passive"))
      (node (ref "R31") (pin "1") (pinfunction "1_1") (pintype "passive"))
      (node (ref "R32") (pin "1") (pinfunction "1_1") (pintype "passive"))
      (node (ref "R33") (pin "1") (pinfunction "1_1") (pintype "passive"))
      (node (ref "U3") (pin "A1") (pinfunction "DNU_A1") (pintype "passive"))
      (node (ref "U3") (pin "A10") (pinfunction "DNU_A10") (pintype "passive"))
      (node (ref "U3") (pin "A2") (pinfunction "DNU_A2") (pintype "passive"))
      (node (ref "U3") (pin "A9") (pinfunction "DNU_A9") (pintype "passive"))
      (node (ref "U3") (pin "B1") (pinfunction "DNU_B1") (pintype "passive"))
      (node (ref "U3") (pin "B10") (pinfunction "DNU_B10") (pintype "passive"))
      (node (ref "U3") (pin "C2") (pinfunction "VSS_C2") (pintype "passive"))
      (node (ref "U3") (pin "C5") (pinfunction "VSS_C5") (pintype "passive"))
      (node (ref "U3") (pin "C6") (pinfunction "VSSQ_C6") (pintype "passive"))
      (node (ref "U3") (pin "C9") (pinfunction "VSSQ_C9") (pintype "passive"))
      (node (ref "U3") (pin "D1") (pinfunction "VSS_D1") (pintype "passive"))
      (node (ref "U3") (pin "D10") (pinfunction "VSSQ_D10") (pintype "passive"))
      (node (ref "U3") (pin "E1") (pinfunction "VSSCA_E1") (pintype "passive"))
      (node (ref "U3") (pin "E10") (pinfunction "VSSQ_E10") (pintype "passive"))
      (node (ref "U3") (pin "F5") (pinfunction "VSSQ_F5") (pintype "passive"))
      (node (ref "U3") (pin "G10") (pinfunction "VSSQ_G10") (pintype "passive"))
      (node (ref "U3") (pin "H2") (pinfunction "VSS_H2") (pintype "passive"))
      (node (ref "U3") (pin "J1") (pinfunction "VSSCA_J1") (pintype "passive"))
      (node (ref "U3") (pin "J5") (pinfunction "VSSQ_J5") (pintype "passive"))
      (node (ref "U3") (pin "J8") (pinfunction "VSS_J8") (pintype "passive"))
      (node (ref "U3") (pin "L10") (pinfunction "VSSQ_L10") (pintype "passive"))
      (node (ref "U3") (pin "M5") (pinfunction "VSSQ_M5") (pintype "passive"))
      (node (ref "U3") (pin "N1") (pinfunction "VSSCA_N1") (pintype "passive"))
      (node (ref "U3") (pin "N10") (pinfunction "VSSQ_N10") (pintype "passive"))
      (node (ref "U3") (pin "P1") (pinfunction "VSS_P1") (pintype "passive"))
      (node (ref "U3") (pin "P10") (pinfunction "VSSQ_P10") (pintype "passive"))
      (node (ref "U3") (pin "R2") (pinfunction "VSS_R2") (pintype "passive"))
      (node (ref "U3") (pin "R5") (pinfunction "VSS_R5") (pintype "passive"))
      (node (ref "U3") (pin "R6") (pinfunction "VSSQ_R6") (pintype "passive"))
      (node (ref "U3") (pin "R9") (pinfunction "VSSQ_R9") (pintype "passive"))
      (node (ref "U3") (pin "T1") (pinfunction "DNU_T1") (pintype "passive"))
      (node (ref "U3") (pin "T10") (pinfunction "DNU_T10") (pintype "passive"))
      (node (ref "U3") (pin "U1") (pinfunction "DNU_U1") (pintype "passive"))
      (node (ref "U3") (pin "U10") (pinfunction "DNU_U10") (pintype "passive"))
      (node (ref "U3") (pin "U2") (pinfunction "DNU_U2") (pintype "passive"))
      (node (ref "U3") (pin "U9") (pinfunction "DNU_U9") (pintype "passive"))
      (node (ref "U4") (pin "A6") (pinfunction "VSS1_A6") (pintype "passive"))
      (node (ref "U4") (pin "C4") (pinfunction "VSSQ1_C4") (pintype "passive"))
      (node (ref "U4") (pin "E7") (pinfunction "VSS2_E7") (pintype "passive"))
      (node (ref "U4") (pin "G5") (pinfunction "VSS3_G5") (pintype "passive"))
      (node (ref "U4") (pin "H10") (pinfunction "VSS4_H10") (pintype "passive"))
      (node (ref "U4") (pin "J5") (pinfunction "VSS5_J5") (pintype "passive"))
      (node (ref "U4") (pin "K8") (pinfunction "VSS6_K8") (pintype "passive"))
      (node (ref "U4") (pin "N2") (pinfunction "VSSQ2_N2") (pintype "passive"))
      (node (ref "U4") (pin "N5") (pinfunction "VSSQ3_N5") (pintype "passive"))
      (node (ref "U4") (pin "P4") (pinfunction "VSSQ4_P4") (pintype "passive"))
      (node (ref "U4") (pin "P6") (pinfunction "VSSQ5_P6") (pintype "passive"))
    )
    (net (code "63") (name "NVCC_3V15") (class "Default")
      (node (ref "C82") (pin "2") (pinfunction "2_2") (pintype "passive"))
      (node (ref "C83") (pin "2") (pinfunction "2_2") (pintype "passive"))
      (node (ref "U4") (pin "C6") (pinfunction "VCCQ1_C6") (pintype "passive"))
      (node (ref "U4") (pin "M4") (pinfunction "VCCQ2_M4") (pintype "passive"))
      (node (ref "U4") (pin "N4") (pinfunction "VCCQ3_N4") (pintype "passive"))
      (node (ref "U4") (pin "P3") (pinfunction "VCCQ4_P3") (pintype "passive"))
      (node (ref "U4") (pin "P5") (pinfunction "VCCQ5_P5") (pintype "passive"))
    )
    (net (code "64") (name "NVCC_DRAM") (class "Default")
      (node (ref "C100") (pin "2") (pinfunction "2_2") (pintype "passive"))
      (node (ref "C101") (pin "2") (pinfunction "2_2") (pintype "passive"))
      (node (ref "C102") (pin "2") (pinfunction "2_2") (pintype "passive"))
      (node (ref "C103") (pin "2") (pinfunction "2_2") (pintype "passive"))
      (node (ref "C104") (pin "2") (pinfunction "2_2") (pintype "passive"))
      (node (ref "C105") (pin "2") (pinfunction "2_2") (pintype "passive"))
      (node (ref "C106") (pin "2") (pinfunction "2_2") (pintype "passive"))
      (node (ref "C107") (pin "2") (pinfunction "2_2") (pintype "passive"))
      (node (ref "C68") (pin "2") (pinfunction "2_2") (pintype "passive"))
      (node (ref "C70") (pin "2") (pinfunction "2_2") (pintype "passive"))
      (node (ref "C71") (pin "2") (pinfunction "2_2") (pintype "passive"))
      (node (ref "C72") (pin "2") (pinfunction "2_2") (pintype "passive"))
      (node (ref "C73") (pin "2") (pinfunction "2_2") (pintype "passive"))
      (node (ref "C74") (pin "2") (pinfunction "2_2") (pintype "passive"))
      (node (ref "C84") (pin "2") (pinfunction "2_2") (pintype "passive"))
      (node (ref "C85") (pin "2") (pinfunction "2_2") (pintype "passive"))
      (node (ref "C86") (pin "2") (pinfunction "2_2") (pintype "passive"))
      (node (ref "C87") (pin "2") (pinfunction "2_2") (pintype "passive"))
      (node (ref "C88") (pin "2") (pinfunction "2_2") (pintype "passive"))
      (node (ref "C89") (pin "2") (pinfunction "2_2") (pintype "passive"))
      (node (ref "C90") (pin "2") (pinfunction "2_2") (pintype "passive"))
      (node (ref "C91") (pin "2") (pinfunction "2_2") (pintype "passive"))
      (node (ref "C92") (pin "2") (pinfunction "2_2") (pintype "passive"))
      (node (ref "C93") (pin "2") (pinfunction "2_2") (pintype "passive"))
      (node (ref "C94") (pin "2") (pinfunction "2_2") (pintype "passive"))
      (node (ref "C95") (pin "2") (pinfunction "2_2") (pintype "passive"))
      (node (ref "C96") (pin "2") (pinfunction "2_2") (pintype "passive"))
      (node (ref "C97") (pin "2") (pinfunction "2_2") (pintype "passive"))
      (node (ref "C98") (pin "2") (pinfunction "2_2") (pintype "passive"))
      (node (ref "C99") (pin "2") (pinfunction "2_2") (pintype "passive"))
      (node (ref "U2") (pin "AA19") (pinfunction "NVCC_DRAM_07_AA19") (pintype "passive"))
      (node (ref "U2") (pin "AC19") (pinfunction "NVCC_DRAM_08_AC19") (pintype "passive"))
      (node (ref "U2") (pin "AF17") (pinfunction "NVCC_DRAM_09_AF17") (pintype "passive"))
      (node (ref "U2") (pin "AF18") (pinfunction "NVCC_DRAM_10_AF18") (pintype "passive"))
      (node (ref "U2") (pin "AF19") (pinfunction "NVCC_DRAM_11_AF19") (pintype "passive"))
      (node (ref "U2") (pin "AG18") (pinfunction "NVCC_DRAM_12_AG18") (pintype "passive"))
      (node (ref "U2") (pin "AH18") (pinfunction "NVCC_DRAM_13_AH18") (pintype "passive"))
      (node (ref "U2") (pin "V20") (pinfunction "NVCC_DRAM_CKE_V20") (pintype "passive"))
      (node (ref "U2") (pin "V27") (pinfunction "NVCC_DRAM_01_V27") (pintype "passive"))
      (node (ref "U2") (pin "V28") (pinfunction "NVCC_DRAM_02_V28") (pintype "passive"))
      (node (ref "U2") (pin "W21") (pinfunction "NVCC_DRAM_03_W21") (pintype "passive"))
      (node (ref "U2") (pin "W23") (pinfunction "NVCC_DRAM_04_W23") (pintype "passive"))
      (node (ref "U2") (pin "W26") (pinfunction "NVCC_DRAM_05_W26") (pintype "passive"))
      (node (ref "U2") (pin "Y20") (pinfunction "NVCC_DRAM_06_Y20") (pintype "passive"))
      (node (ref "U3") (pin "B5") (pinfunction "VDD2_B5") (pintype "passive"))
      (node (ref "U3") (pin "C10") (pinfunction "VDDQ_C10") (pintype "passive"))
      (node (ref "U3") (pin "C7") (pinfunction "VDDQ_C7") (pintype "passive"))
      (node (ref "U3") (pin "D2") (pinfunction "VDD2_D2") (pintype "passive"))
      (node (ref "U3") (pin "D5") (pinfunction "VDDQ_D5") (pintype "passive"))
      (node (ref "U3") (pin "E9") (pinfunction "VDDQ_E9") (pintype "passive"))
      (node (ref "U3") (pin "F1") (pinfunction "VDDCA_F1") (pintype "passive"))
      (node (ref "U3") (pin "F10") (pinfunction "VDDQ_F10") (pintype "passive"))
      (node (ref "U3") (pin "G1") (pinfunction "VDD2_G1") (pintype "passive"))
      (node (ref "U3") (pin "H1") (pinfunction "VDDCA_H1") (pintype "passive"))
      (node (ref "U3") (pin "H6") (pinfunction "VDDQ_H6") (pintype "passive"))
      (node (ref "U3") (pin "J6") (pinfunction "VDDQ_J6") (pintype "passive"))
      (node (ref "U3") (pin "J7") (pinfunction "VDD2_J7") (pintype "passive"))
      (node (ref "U3") (pin "K6") (pinfunction "VDDQ_K6") (pintype "passive"))
      (node (ref "U3") (pin "M10") (pinfunction "VDDQ_M10") (pintype "passive"))
      (node (ref "U3") (pin "N2") (pinfunction "VDDCA_N2") (pintype "passive"))
      (node (ref "U3") (pin "N9") (pinfunction "VDDQ_N9") (pintype "passive"))
      (node (ref "U3") (pin "P2") (pinfunction "VDD2_P2") (pintype "passive"))
      (node (ref "U3") (pin "P5") (pinfunction "VDDQ_P5") (pintype "passive"))
      (node (ref "U3") (pin "R10") (pinfunction "VDDQ_R10") (pintype "passive"))
      (node (ref "U3") (pin "R7") (pinfunction "VDDQ_R7") (pintype "passive"))
      (node (ref "U3") (pin "T5") (pinfunction "VDD2_T5") (pintype "passive"))
    )
    (net (code "65") (name "Net-(U2D-DRAM_ZQPAD)") (class "Default")
      (node (ref "R33") (pin "2") (pinfunction "2_2") (pintype "passive"))
      (node (ref "U2") (pin "Y18") (pinfunction "DRAM_ZQPAD_Y18") (pintype "passive"))
    )
    (net (code "66") (name "Net-(U3A-ZQ0)") (class "Default")
      (node (ref "R30") (pin "2") (pinfunction "2_2") (pintype "passive"))
      (node (ref "U3") (pin "D3") (pinfunction "ZQ0_D3") (pintype "passive"))
    )
    (net (code "67") (name "Net-(U3A-ZQ1)") (class "Default")
      (node (ref "R31") (pin "2") (pinfunction "2_2") (pintype "passive"))
      (node (ref "U3") (pin "C3") (pinfunction "ZQ1_C3") (pintype "passive"))
    )
    (net (code "68") (name "Net-(U4-VDDIM)") (class "Default")
      (node (ref "C67") (pin "2") (pinfunction "2_2") (pintype "passive"))
      (node (ref "U4") (pin "C2") (pinfunction "VDDIM_C2") (pintype "passive"))
    )
    (net (code "69") (name "PERI_3V15") (class "Default")
      (node (ref "C80") (pin "2") (pinfunction "2_2") (pintype "passive"))
      (node (ref "C81") (pin "2") (pinfunction "2_2") (pintype "passive"))
      (node (ref "U4") (pin "E6") (pinfunction "VCC1_E6") (pintype "passive"))
      (node (ref "U4") (pin "F5") (pinfunction "VCC2_F5") (pintype "passive"))
      (node (ref "U4") (pin "J10") (pinfunction "VCC3_J10") (pintype "passive"))
      (node (ref "U4") (pin "K9") (pinfunction "VCC4_K9") (pintype "passive"))
    )
    (net (code "70") (name "SD3_CLK") (class "Default")
      (node (ref "U4") (pin "M6") (pinfunction "CLK_M6") (pintype "input"))
    )
    (net (code "71") (name "SD3_CMD") (class "Default")
      (node (ref "U4") (pin "M5") (pinfunction "CMD_M5") (pintype "passive"))
    )
    (net (code "72") (name "SD3_DATA0") (class "Default")
      (node (ref "U4") (pin "A3") (pinfunction "DAT0_A3") (pintype "passive"))
    )
    (net (code "73") (name "SD3_DATA1") (class "Default")
      (node (ref "U4") (pin "A4") (pinfunction "DAT1_A4") (pintype "passive"))
    )
    (net (code "74") (name "SD3_DATA2") (class "Default")
      (node (ref "U4") (pin "A5") (pinfunction "DAT2_A5") (pintype "passive"))
    )
    (net (code "75") (name "SD3_DATA3") (class "Default")
      (node (ref "U4") (pin "B2") (pinfunction "DAT3_B2") (pintype "passive"))
    )
    (net (code "76") (name "SD3_DATA4") (class "Default")
      (node (ref "U4") (pin "B3") (pinfunction "DAT4_B3") (pintype "passive"))
    )
    (net (code "77") (name "SD3_DATA5") (class "Default")
      (node (ref "U4") (pin "B4") (pinfunction "DAT5_B4") (pintype "passive"))
    )
    (net (code "78") (name "SD3_DATA6") (class "Default")
      (node (ref "U4") (pin "B5") (pinfunction "DAT6_B5") (pintype "passive"))
    )
    (net (code "79") (name "SD3_DATA7") (class "Default")
      (node (ref "U4") (pin "B6") (pinfunction "DAT7_B6") (pintype "passive"))
    )
    (net (code "80") (name "SD3_RESET_B") (class "Default")
      (node (ref "U4") (pin "K5") (pinfunction "~{RESET}_K5") (pintype "input"))
    )
    (net (code "81") (name "SD3_STROBE") (class "Default")
      (node (ref "U4") (pin "H5") (pinfunction "DATA_STROBE_H5") (pintype "output"))
    )
    (net (code "82") (name "SW2_1V8") (class "Default")
      (node (ref "C75") (pin "2") (pinfunction "2_2") (pintype "passive"))
      (node (ref "C76") (pin "2") (pinfunction "2_2") (pintype "passive"))
      (node (ref "C77") (pin "2") (pinfunction "2_2") (pintype "passive"))
      (node (ref "C78") (pin "2") (pinfunction "2_2") (pintype "passive"))
      (node (ref "C79") (pin "2") (pinfunction "2_2") (pintype "passive"))
      (node (ref "U3") (pin "B6") (pinfunction "VDD1_B6") (pintype "passive"))
      (node (ref "U3") (pin "C1") (pinfunction "VDD1_C1") (pintype "passive"))
      (node (ref "U3") (pin "R1") (pinfunction "VDD1_R1") (pintype "passive"))
      (node (ref "U3") (pin "T6") (pinfunction "VDD1_T6") (pintype "passive"))
    )
    (net (code "83") (name "unconnected-(U2D-DRAM_ADDR10-PadAD23)") (class "Default")
      (node (ref "U2") (pin "AD23") (pinfunction "DRAM_ADDR10_AD23") (pintype "passive+no_connect"))
    )
    (net (code "84") (name "unconnected-(U2D-DRAM_ADDR11-PadAG27)") (class "Default")
      (node (ref "U2") (pin "AG27") (pinfunction "DRAM_ADDR11_AG27") (pintype "passive+no_connect"))
    )
    (net (code "85") (name "unconnected-(U2D-DRAM_ADDR12-PadAE27)") (class "Default")
      (node (ref "U2") (pin "AE27") (pinfunction "DRAM_ADDR12_AE27") (pintype "passive+no_connect"))
    )
    (net (code "86") (name "unconnected-(U2D-DRAM_ADDR13-PadAG28)") (class "Default")
      (node (ref "U2") (pin "AG28") (pinfunction "DRAM_ADDR13_AG28") (pintype "passive+no_connect"))
    )
    (net (code "87") (name "unconnected-(U2D-DRAM_ADDR14-PadAE20)") (class "Default")
      (node (ref "U2") (pin "AE20") (pinfunction "DRAM_ADDR14_AE20") (pintype "passive+no_connect"))
    )
    (net (code "88") (name "unconnected-(U2D-DRAM_ADDR15-PadAG26)") (class "Default")
      (node (ref "U2") (pin "AG26") (pinfunction "DRAM_ADDR15_AG26") (pintype "passive+no_connect"))
    )
    (net (code "89") (name "unconnected-(U2D-DRAM_ODT0-PadAF16)") (class "Default")
      (node (ref "U2") (pin "AF16") (pinfunction "DRAM_ODT0_AF16") (pintype "passive+no_connect"))
    )
    (net (code "90") (name "unconnected-(U2D-DRAM_RESET-PadV26)") (class "Default")
      (node (ref "U2") (pin "V26") (pinfunction "DRAM_RESET_V26") (pintype "passive+no_connect"))
    )
    (net (code "91") (name "unconnected-(U2D-DRAM_SDBA0-PadAE28)") (class "Default")
      (node (ref "U2") (pin "AE28") (pinfunction "DRAM_SDBA0_AE28") (pintype "passive+no_connect"))
    )
    (net (code "92") (name "unconnected-(U2D-DRAM_SDBA1-PadAB22)") (class "Default")
      (node (ref "U2") (pin "AB22") (pinfunction "DRAM_SDBA1_AB22") (pintype "passive+no_connect"))
    )
    (net (code "93") (name "unconnected-(U2D-DRAM_SDBA2-PadAF27)") (class "Default")
      (node (ref "U2") (pin "AF27") (pinfunction "DRAM_SDBA2_AF27") (pintype "passive+no_connect"))
    )
    (net (code "94") (name "unconnected-(U2D-DRAM_SDCKE1-PadAB23)") (class "Default")
      (node (ref "U2") (pin "AB23") (pinfunction "DRAM_SDCKE1_AB23") (pintype "passive+no_connect"))
    )
    (net (code "95") (name "unconnected-(U2D-DRAM_SDWE-PadAH27)") (class "Default")
      (node (ref "U2") (pin "AH27") (pinfunction "DRAM_SDWE_AH27") (pintype "passive+no_connect"))
    )
    (net (code "96") (name "unconnected-(U2D-DRAM_~{CAS}-PadAG25)") (class "Default")
      (node (ref "U2") (pin "AG25") (pinfunction "DRAM_~{CAS}_AG25") (pintype "passive+no_connect"))
    )
    (net (code "97") (name "unconnected-(U2D-DRAM_~{CS1}-PadAC23)") (class "Default")
      (node (ref "U2") (pin "AC23") (pinfunction "DRAM_~{CS1}_AC23") (pintype "passive+no_connect"))
    )
    (net (code "98") (name "unconnected-(U2D-DRAM_~{RAS}-PadAH25)") (class "Default")
      (node (ref "U2") (pin "AH25") (pinfunction "DRAM_~{RAS}_AH25") (pintype "passive+no_connect"))
    )
    (net (code "99") (name "unconnected-(U3C-NC-PadB2)") (class "Default")
      (node (ref "U3") (pin "B2") (pinfunction "NC_B2") (pintype "passive+no_connect"))
    )
    (net (code "100") (name "unconnected-(U3C-NC-PadB3)") (class "Default")
      (node (ref "U3") (pin "B3") (pinfunction "NC_B3") (pintype "passive+no_connect"))
    )
    (net (code "101") (name "unconnected-(U3C-NC-PadJ2)") (class "Default")
      (node (ref "U3") (pin "J2") (pinfunction "NC_J2") (pintype "passive+no_connect"))
    )
    (net (code "102") (name "unconnected-(U3C-NC-PadR3)") (class "Default")
      (node (ref "U3") (pin "R3") (pinfunction "NC_R3") (pintype "passive+no_connect"))
    )
    (net (code "103") (name "unconnected-(U3C-NC-PadT2)") (class "Default")
      (node (ref "U3") (pin "T2") (pinfunction "NC_T2") (pintype "passive+no_connect"))
    )
    (net (code "104") (name "unconnected-(U3C-NC-PadT3)") (class "Default")
      (node (ref "U3") (pin "T3") (pinfunction "NC_T3") (pintype "passive+no_connect"))
    )
    (net (code "105") (name "unconnected-(U3C-RFU-PadK2)") (class "Default")
      (node (ref "U3") (pin "K2") (pinfunction "RFU_K2") (pintype "passive+no_connect"))
    )
    (net (code "106") (name "unconnected-(U3C-RFU-PadK3)") (class "Default")
      (node (ref "U3") (pin "K3") (pinfunction "RFU_K3") (pintype "passive+no_connect"))
    )
    (net (code "107") (name "unconnected-(U3C-RFU-PadL2)") (class "Default")
      (node (ref "U3") (pin "L2") (pinfunction "RFU_L2") (pintype "passive+no_connect"))
    )
    (net (code "108") (name "unconnected-(U3C-RFU-PadL3)") (class "Default")
      (node (ref "U3") (pin "L3") (pinfunction "RFU_L3") (pintype "passive+no_connect"))
    )
  )
)
